# COMMOM.net
KiCad netlist of a schematic drawn in Altium Designer
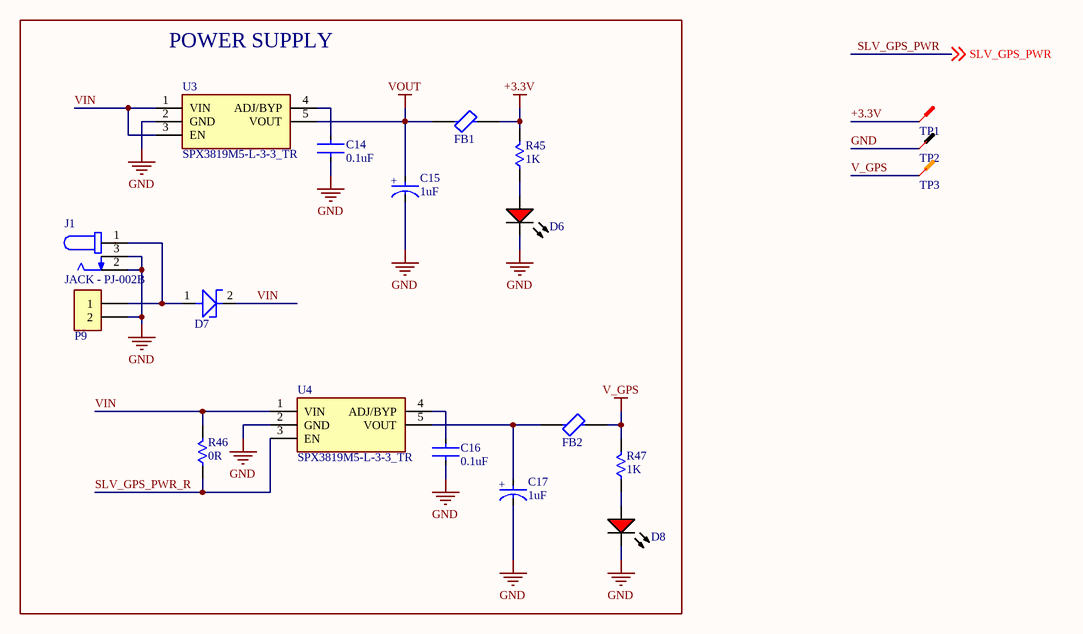
[diagram p0: COMMOM.SchDoc]

(export (version "E")
  (design (tool "Eeschema 10.0.6"))
  (components
    (comp (ref "C14")
      (value "0.1uF")
      (footprint "0805-CAP")
      (description "CAP CER SMD 0805, 0.1uF / 16V, ±10%")
      (fields
        (field (name "MANUFACTURER") "Yageo")
        (field (name "MANUFACTURER PART NUMBER") "AC0805KRX7R7BB104")
      )
      (libsource (lib "Capacitor") (part "AC0805KRX7R7BB104"))
    )
    (comp (ref "C15")
      (value "1uF")
      (footprint "1206-CAP-TANT")
      (description "CAP TANT SMD 1206, 1uF / 20V, ±10%")
      (fields
        (field (name "MANUFACTURER") "Kyocera AVX")
        (field (name "MANUFACTURER PART NUMBER") "TAJA105K020RNJ")
      )
      (libsource (lib "Capacitor") (part "TAJA105K020RNJ"))
    )
    (comp (ref "C16")
      (value "0.1uF")
      (footprint "0805-CAP")
      (description "CAP CER SMD 0805, 0.1uF / 16V, ±10%")
      (fields
        (field (name "MANUFACTURER") "Yageo")
        (field (name "MANUFACTURER PART NUMBER") "AC0805KRX7R7BB104")
      )
      (libsource (lib "Capacitor") (part "AC0805KRX7R7BB104"))
    )
    (comp (ref "C17")
      (value "1uF")
      (footprint "1206-CAP-TANT")
      (description "CAP TANT SMD 1206, 1uF / 20V, ±10%")
      (fields
        (field (name "MANUFACTURER") "Kyocera AVX")
        (field (name "MANUFACTURER PART NUMBER") "TAJA105K020RNJ")
      )
      (libsource (lib "Capacitor") (part "TAJA105K020RNJ"))
    )
    (comp (ref "D6")
      (value "RED")
      (footprint "0805-LED-RED")
      (description "LED RED, SMD 0805, 2V/30mA")
      (fields
        (field (name "MANUFACTURER") "Vishay Lite-On")
        (field (name "MANUFACTURER PART NUMBER") "LTST-C170EKT")
      )
      (libsource (lib "Diode") (part "LTST-C170EKT"))
    )
    (comp (ref "D7")
      (value "NRVB120VLSFT1G")
      (footprint "SOD-123")
      (description "DIODE SHOTTKY SMD SOD-123F, 0,3V/1A, VBR 20V")
      (fields (field (name "MANUFACTURER") "ON Semiconductor"))
      (libsource (lib "Diode") (part "NRVB120VLSFT1G"))
    )
    (comp (ref "D8")
      (value "RED")
      (footprint "0805-LED-RED")
      (description "LED RED, SMD 0805, 2V/30mA")
      (fields
        (field (name "MANUFACTURER") "Vishay Lite-On")
        (field (name "MANUFACTURER PART NUMBER") "LTST-C170EKT")
      )
      (libsource (lib "Diode") (part "LTST-C170EKT"))
    )
    (comp (ref "FB1")
      (value "BLM21BB121SN1D")
      (footprint "0805-IND")
      (description "FERRITE BEAD SMD 0805, 120Ω/100MHz, DC_RES=0.19Ω, 600mA")
      (fields (field (name "MANUFACTURER") "Murata") (field (name "TOLERANCE") "25%"))
      (libsource (lib "Inductor") (part "BLM21BB121SN1D"))
    )
    (comp (ref "FB2")
      (value "BLM21BB121SN1D")
      (footprint "0805-IND")
      (description "FERRITE BEAD SMD 0805, 120Ω/100MHz, DC_RES=0.19Ω, 600mA")
      (fields (field (name "MANUFACTURER") "Murata") (field (name "TOLERANCE") "25%"))
      (libsource (lib "Inductor") (part "BLM21BB121SN1D"))
    )
    (comp (ref "J1")
      (value "JACK - PJ-002B")
      (footprint "JACK - CUI_PJ-002B")
      (description "CONN PWR JACK 2.5X5.5MM SOLDER")
      (fields (field (name "MANUFACTURER") "CUI") (field (name "MANUFACTURER PART NUMBER") "PJ-002B"))
      (libsource (lib "Connector") (part "JACK - PJ-002B"))
    )
    (comp (ref "P9")
      (value "691312510002")
      (footprint "691312510002")
      (description "312; 5.08mm Pitch Straight Pluggable Term Block; PCB Header; Through Hole; 2 Way")
      (fields (field (name "MANUFACTURER") "Wurth Electronics") (field (name "VOLTAGE") "300V"))
      (libsource (lib "Connector") (part "691312510002"))
    )
    (comp (ref "R45")
      (value "1K")
      (footprint "0805-RES")
      (description "Res Thin Film 0805 1K Ohm 1% 0.25W(1/4W) ±100ppm/C Sulfur Resistant Pad SMD T/R")
      (fields
        (field (name "MANUFACTURER") "Stackpole Electronics")
        (field (name "MANUFACTURER PART NUMBER") "RNCP0805FTD1K00")
      )
      (libsource (lib "Resistor") (part "RNCP0805FTD1K00"))
    )
    (comp (ref "R46")
      (value "0R")
      (footprint "0805-RES")
      (description "RES SMD 0805, 0 OHM JUMPER 1/8W")
      (fields (field (name "TOLERANCE") "5%") (field (name "MANUFACTURER PART NUMBER") "RC0805JR-070RL"))
      (libsource (lib "Resistor") (part "RC0805JR-070RL"))
    )
    (comp (ref "R47")
      (value "1K")
      (footprint "0805-RES")
      (description "Res Thin Film 0805 1K Ohm 1% 0.25W(1/4W) ±100ppm/C Sulfur Resistant Pad SMD T/R")
      (fields
        (field (name "MANUFACTURER") "Stackpole Electronics")
        (field (name "MANUFACTURER PART NUMBER") "RNCP0805FTD1K00")
      )
      (libsource (lib "Resistor") (part "RNCP0805FTD1K00"))
    )
    (comp (ref "TP1")
      (value ".Net")
      (footprint "TESTPOINT_MINI_RED")
      (description "PC TEST POINT MINIATURE RED")
      (libsource (lib "Connector") (part "TESTPOINT 5000"))
    )
    (comp (ref "TP2")
      (value ".Net")
      (footprint "TESTPOINT_MINI_BLACK")
      (description "PC TEST POINT MINIATURE BLACK")
      (libsource (lib "Connector") (part "TESTPOINT 5001"))
    )
    (comp (ref "TP3")
      (value "5003")
      (footprint "TESTPOINT_MINI_ORANGE")
      (description "PC TEST POINT MINIATURE ORANGE")
      (libsource (lib "Connector") (part "TESTPOINT 5003"))
    )
    (comp (ref "U3")
      (value "SPX3819M5-L-3-3_TR")
      (footprint "SPX3819M5-L-3-3_TR")
      (description "IC REG LDO 3.3V 0.5A SOT23-5")
      (fields
        (field (name "MANUFACTURER PART NUMBER") "SPX3819M5-L-3-3/TR")
        (field (name "MANUFACTURER") "Exar")
      )
      (libsource (lib "IC") (part "SPX3819M5-L-3-3_TR"))
    )
    (comp (ref "U4")
      (value "SPX3819M5-L-3-3_TR")
      (footprint "SPX3819M5-L-3-3_TR")
      (description "IC REG LDO 3.3V 0.5A SOT23-5")
      (fields
        (field (name "MANUFACTURER") "Exar")
        (field (name "MANUFACTURER PART NUMBER") "SPX3819M5-L-3-3/TR")
      )
      (libsource (lib "IC") (part "SPX3819M5-L-3-3_TR"))
    )
  )
  (nets
    (net (code "1") (name "+3.3V") (class "Default")
      (node (ref "FB1") (pin "2") (pinfunction "2_2") (pintype "passive"))
      (node (ref "R45") (pin "2") (pinfunction "2_2") (pintype "passive"))
      (node (ref "TP1") (pin "1") (pinfunction "1_1") (pintype "passive"))
    )
    (net (code "2") (name "/SLV_GPS_PWR_R") (class "Default")
      (node (ref "R46") (pin "1") (pinfunction "1_1") (pintype "passive"))
      (node (ref "U4") (pin "3") (pinfunction "EN_3") (pintype "passive"))
    )
    (net (code "3") (name "/VIN") (class "Default")
      (node (ref "D7") (pin "2") (pinfunction "2_2") (pintype "passive"))
      (node (ref "R46") (pin "2") (pinfunction "2_2") (pintype "passive"))
      (node (ref "U3") (pin "1") (pinfunction "VIN_1") (pintype "passive"))
      (node (ref "U3") (pin "3") (pinfunction "EN_3") (pintype "passive"))
      (node (ref "U4") (pin "1") (pinfunction "VIN_1") (pintype "passive"))
    )
    (net (code "4") (name "GND") (class "Default")
      (node (ref "C14") (pin "2") (pinfunction "2_2") (pintype "passive"))
      (node (ref "C15") (pin "2") (pinfunction "C_2") (pintype "passive"))
      (node (ref "C16") (pin "2") (pinfunction "2_2") (pintype "passive"))
      (node (ref "C17") (pin "2") (pinfunction "C_2") (pintype "passive"))
      (node (ref "D6") (pin "2") (pinfunction "K_2") (pintype "passive"))
      (node (ref "D8") (pin "2") (pinfunction "K_2") (pintype "passive"))
      (node (ref "J1") (pin "2") (pinfunction "2_2") (pintype "passive"))
      (node (ref "J1") (pin "3") (pinfunction "3_3") (pintype "passive"))
      (node (ref "P9") (pin "2") (pinfunction "2_2") (pintype "passive"))
      (node (ref "TP2") (pin "1") (pinfunction "1_1") (pintype "passive"))
      (node (ref "U3") (pin "2") (pinfunction "GND_2") (pintype "passive"))
      (node (ref "U4") (pin "2") (pinfunction "GND_2") (pintype "passive"))
    )
    (net (code "5") (name "Net-(C17-A)") (class "Default")
      (node (ref "C17") (pin "1") (pinfunction "A_1") (pintype "passive"))
      (node (ref "FB2") (pin "1") (pinfunction "1_1") (pintype "passive"))
      (node (ref "U4") (pin "5") (pinfunction "VOUT_5") (pintype "passive"))
    )
    (net (code "6") (name "Net-(D6-A)") (class "Default")
      (node (ref "D6") (pin "1") (pinfunction "A_1") (pintype "passive"))
      (node (ref "R45") (pin "1") (pinfunction "1_1") (pintype "passive"))
    )
    (net (code "7") (name "Net-(D7-Pad1)") (class "Default")
      (node (ref "D7") (pin "1") (pinfunction "1_1") (pintype "passive"))
      (node (ref "J1") (pin "1") (pinfunction "1_1") (pintype "passive"))
      (node (ref "P9") (pin "1") (pinfunction "1_1") (pintype "passive"))
    )
    (net (code "8") (name "Net-(D8-A)") (class "Default")
      (node (ref "D8") (pin "1") (pinfunction "A_1") (pintype "passive"))
      (node (ref "R47") (pin "1") (pinfunction "1_1") (pintype "passive"))
    )
    (net (code "9") (name "Net-(U3-ADJ{slash}BYP)") (class "Default")
      (node (ref "C14") (pin "1") (pinfunction "1_1") (pintype "passive"))
      (node (ref "U3") (pin "4") (pinfunction "ADJ/BYP_4") (pintype "passive"))
    )
    (net (code "10") (name "Net-(U4-ADJ{slash}BYP)") (class "Default")
      (node (ref "C16") (pin "1") (pinfunction "1_1") (pintype "passive"))
      (node (ref "U4") (pin "4") (pinfunction "ADJ/BYP_4") (pintype "passive"))
    )
    (net (code "12") (name "VOUT") (class "Default")
      (node (ref "C15") (pin "1") (pinfunction "A_1") (pintype "passive"))
      (node (ref "FB1") (pin "1") (pinfunction "1_1") (pintype "passive"))
      (node (ref "U3") (pin "5") (pinfunction "VOUT_5") (pintype "passive"))
    )
    (net (code "13") (name "V_GPS") (class "Default")
      (node (ref "FB2") (pin "2") (pinfunction "2_2") (pintype "passive"))
      (node (ref "R47") (pin "2") (pinfunction "2_2") (pintype "passive"))
      (node (ref "TP3") (pin "1") (pinfunction "1_1") (pintype "passive"))
    )
  )
)
